# main.net
KiCad netlist of a schematic drawn in Altium Designer
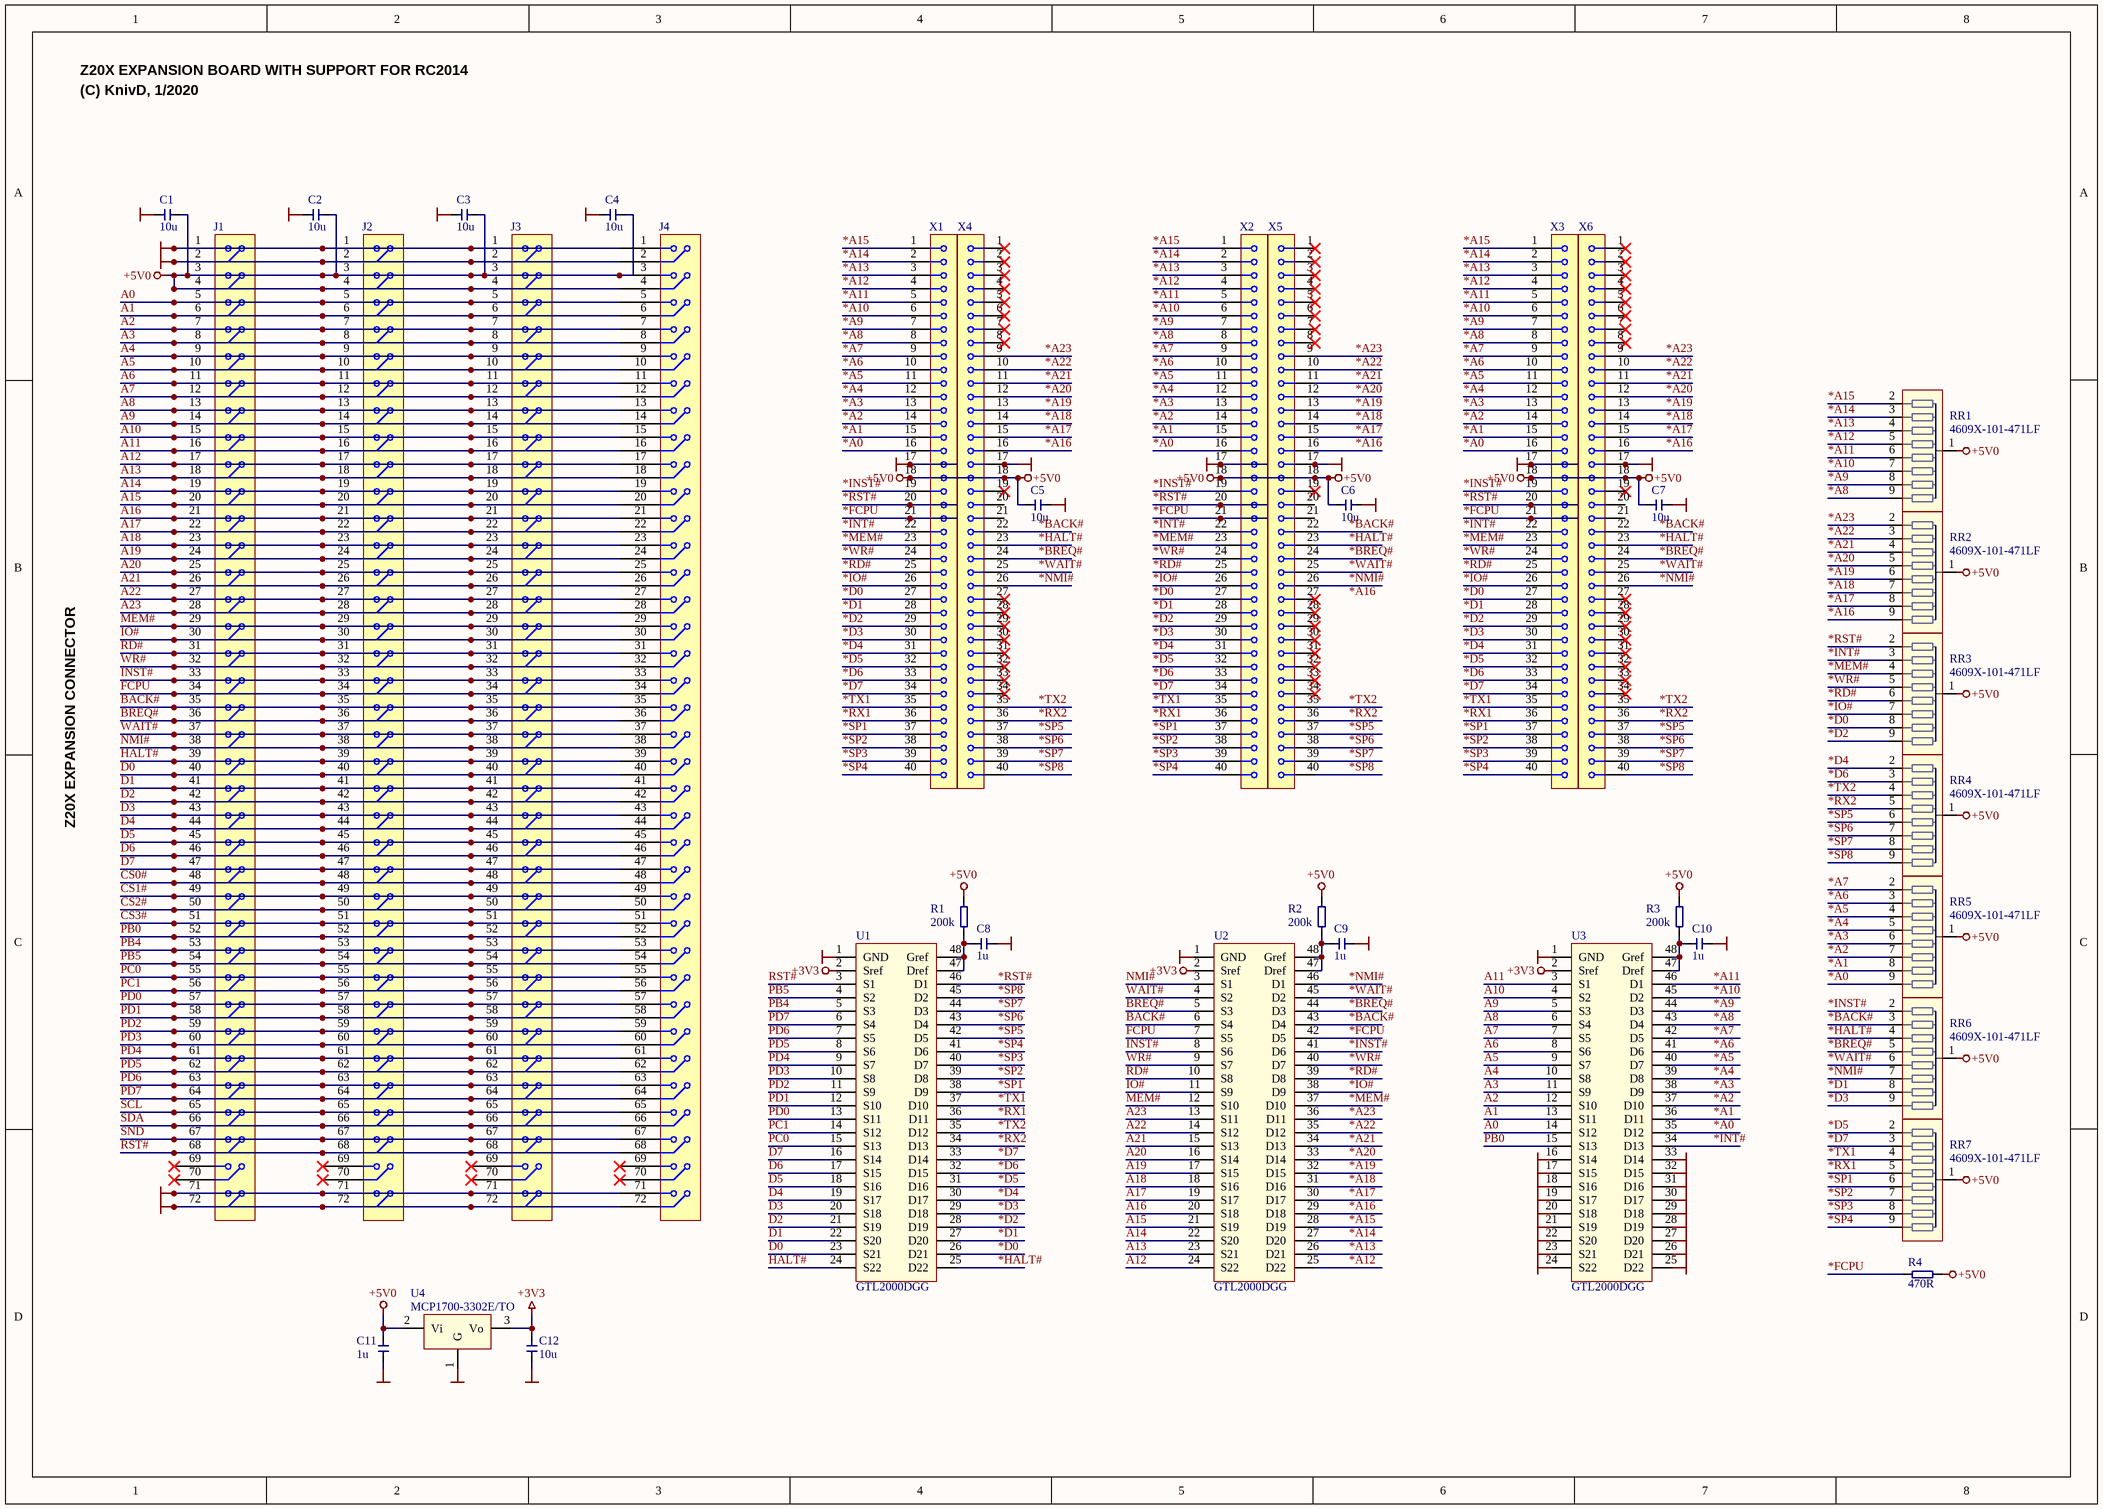
[diagram p0: main.SchDoc]

(export (version "E")
  (design (tool "Eeschema 10.0.6"))
  (components
    (comp (ref "C1")
      (value "10u")
      (footprint "CAPRR508-350X500X500")
      (description "Capacitor")
      (libsource (lib "Discretes") (part "Capacitor"))
    )
    (comp (ref "C2")
      (value "10u")
      (footprint "CAPRR508-350X500X500")
      (description "Capacitor")
      (libsource (lib "Discretes") (part "Capacitor"))
    )
    (comp (ref "C3")
      (value "10u")
      (footprint "CAPRR508-350X500X500")
      (description "Capacitor")
      (libsource (lib "Discretes") (part "Capacitor"))
    )
    (comp (ref "C4")
      (value "10u")
      (footprint "CAPRR508-350X500X500")
      (description "Capacitor")
      (libsource (lib "Discretes") (part "Capacitor"))
    )
    (comp (ref "C5")
      (value "10u")
      (footprint "CAPRR508-350X500X500")
      (description "Capacitor")
      (libsource (lib "Discretes") (part "Capacitor"))
    )
    (comp (ref "C6")
      (value "10u")
      (footprint "CAPRR508-350X500X500")
      (description "Capacitor")
      (libsource (lib "Discretes") (part "Capacitor"))
    )
    (comp (ref "C7")
      (value "10u")
      (footprint "CAPRR508-350X500X500")
      (description "Capacitor")
      (libsource (lib "Discretes") (part "Capacitor"))
    )
    (comp (ref "C8")
      (value "1u")
      (footprint "CAPRR508-350X500X500")
      (description "Capacitor")
      (libsource (lib "Discretes") (part "Capacitor"))
    )
    (comp (ref "C9")
      (value "1u")
      (footprint "CAPRR508-350X500X500")
      (description "Capacitor")
      (libsource (lib "Discretes") (part "Capacitor"))
    )
    (comp (ref "C10")
      (value "1u")
      (footprint "CAPRR508-350X500X500")
      (description "Capacitor")
      (libsource (lib "Discretes") (part "Capacitor"))
    )
    (comp (ref "C11")
      (value "1u")
      (footprint "CAPRR508-350X500X500")
      (description "Capacitor")
      (libsource (lib "Discretes") (part "Capacitor"))
    )
    (comp (ref "C12")
      (value "10u")
      (footprint "CAPRR508-350X500X500")
      (description "Capacitor")
      (libsource (lib "Discretes") (part "Capacitor"))
    )
    (comp (ref "J1")
      (value "~")
      (footprint "2011-2X36S-F")
      (description "Dual row, 72-way connector")
      (libsource (lib "Connectors") (part "Connector 2x36"))
    )
    (comp (ref "J2")
      (value "~")
      (footprint "2011-2X36S-F")
      (description "Dual row, 72-way connector")
      (libsource (lib "Connectors") (part "Connector 2x36"))
    )
    (comp (ref "J3")
      (value "~")
      (footprint "2011-2X36S-F")
      (description "Dual row, 72-way connector")
      (libsource (lib "Connectors") (part "Connector 2x36"))
    )
    (comp (ref "J4")
      (value "~")
      (footprint "2011-2X36S-F")
      (description "Dual row, 72-way connector")
      (libsource (lib "Connectors") (part "Connector 2x36"))
    )
    (comp (ref "R1")
      (value "200k")
      (footprint "RES1016-660X250")
      (description "Resistor")
      (libsource (lib "") (part "Resistor_1"))
    )
    (comp (ref "R2")
      (value "200k")
      (footprint "RES1016-660X250")
      (description "Resistor")
      (libsource (lib "") (part "Resistor_1"))
    )
    (comp (ref "R3")
      (value "200k")
      (footprint "RES1016-660X250")
      (description "Resistor")
      (libsource (lib "") (part "Resistor_1"))
    )
    (comp (ref "R4")
      (value "470R")
      (footprint "RES1016-660X250")
      (description "Resistor")
      (libsource (lib "Discretes") (part "Resistor"))
    )
    (comp (ref "RR1")
      (value "4609X-101-471LF")
      (footprint "RN_BOURNS_4600X")
      (description "Resistor Array (Bussed)")
      (libsource (lib "Misc") (part "Resistor Array x8 (BUSSED)"))
    )
    (comp (ref "RR2")
      (value "4609X-101-471LF")
      (footprint "RN_BOURNS_4600X")
      (description "Resistor Array (Bussed)")
      (libsource (lib "Misc") (part "Resistor Array x8 (BUSSED)"))
    )
    (comp (ref "RR3")
      (value "4609X-101-471LF")
      (footprint "RN_BOURNS_4600X")
      (description "Resistor Array (Bussed)")
      (libsource (lib "Misc") (part "Resistor Array x8 (BUSSED)"))
    )
    (comp (ref "RR4")
      (value "4609X-101-471LF")
      (footprint "RN_BOURNS_4600X")
      (description "Resistor Array (Bussed)")
      (libsource (lib "Misc") (part "Resistor Array x8 (BUSSED)"))
    )
    (comp (ref "RR5")
      (value "4609X-101-471LF")
      (footprint "RN_BOURNS_4600X")
      (description "Resistor Array (Bussed)")
      (libsource (lib "Misc") (part "Resistor Array x8 (BUSSED)"))
    )
    (comp (ref "RR6")
      (value "4609X-101-471LF")
      (footprint "RN_BOURNS_4600X")
      (description "Resistor Array (Bussed)")
      (libsource (lib "Misc") (part "Resistor Array x8 (BUSSED)"))
    )
    (comp (ref "RR7")
      (value "4609X-101-471LF")
      (footprint "RN_BOURNS_4600X")
      (description "Resistor Array (Bussed)")
      (libsource (lib "Misc") (part "Resistor Array x8 (BUSSED)"))
    )
    (comp (ref "U1")
      (value "GTL2000DGG")
      (footprint "SOP50P810X120-48N")
      (description "22-bit bi-directional low voltage translator")
      (fields (field (name "MANUFACTURER") "NXP"))
      (libsource (lib "IC Interface") (part "GTL2000"))
    )
    (comp (ref "U2")
      (value "GTL2000DGG")
      (footprint "SOP50P810X120-48N")
      (description "22-bit bi-directional low voltage translator")
      (fields (field (name "MANUFACTURER") "NXP"))
      (libsource (lib "IC Interface") (part "GTL2000"))
    )
    (comp (ref "U3")
      (value "GTL2000DGG")
      (footprint "SOP50P810X120-48N")
      (description "22-bit bi-directional low voltage translator")
      (fields (field (name "MANUFACTURER") "NXP"))
      (libsource (lib "IC Interface") (part "GTL2000"))
    )
    (comp (ref "U4")
      (value "MCP1700-3302E/TO")
      (footprint "TO-92AA-P254")
      (description "3-terminal 250mA positive voltage regulator")
      (fields (field (name "MANUFACTURER") "Microchip"))
      (libsource (lib "IC Power Supply") (part "78Lxx"))
    )
    (comp (ref "X1")
      (value "SIL40-F")
      (footprint "2011-1X40S")
      (description "Single row, 40-way connector")
      (libsource (lib "Connectors") (part "Connector 1x40"))
    )
    (comp (ref "X2")
      (value "SIL40-F")
      (footprint "2011-1X40S")
      (description "Single row, 40-way connector")
      (libsource (lib "Connectors") (part "Connector 1x40"))
    )
    (comp (ref "X3")
      (value "SIL40-F")
      (footprint "2011-1X40S")
      (description "Single row, 40-way connector")
      (libsource (lib "Connectors") (part "Connector 1x40"))
    )
    (comp (ref "X4")
      (value "SIL40-F")
      (footprint "2011-1X40S")
      (description "Single row, 40-way connector")
      (libsource (lib "Connectors") (part "Connector 1x40"))
    )
    (comp (ref "X5")
      (value "SIL40-F")
      (footprint "2011-1X40S")
      (description "Single row, 40-way connector")
      (libsource (lib "Connectors") (part "Connector 1x40"))
    )
    (comp (ref "X6")
      (value "SIL40-F")
      (footprint "2011-1X40S")
      (description "Single row, 40-way connector")
      (libsource (lib "Connectors") (part "Connector 1x40"))
    )
  )
  (nets
    (net (code "1") (name "+3V3") (class "Default")
      (node (ref "C12") (pin "1") (pintype "passive"))
      (node (ref "U1") (pin "2") (pinfunction "Sref_2") (pintype "passive"))
      (node (ref "U2") (pin "2") (pinfunction "Sref_2") (pintype "passive"))
      (node (ref "U3") (pin "2") (pinfunction "Sref_2") (pintype "passive"))
      (node (ref "U4") (pin "3") (pinfunction "Vo_3") (pintype "passive"))
    )
    (net (code "2") (name "+5V0") (class "Default")
      (node (ref "C1") (pin "1") (pintype "passive"))
      (node (ref "C11") (pin "1") (pintype "passive"))
      (node (ref "C2") (pin "1") (pintype "passive"))
      (node (ref "C3") (pin "1") (pintype "passive"))
      (node (ref "C4") (pin "1") (pintype "passive"))
      (node (ref "C5") (pin "2") (pintype "passive"))
      (node (ref "C6") (pin "2") (pintype "passive"))
      (node (ref "C7") (pin "2") (pintype "passive"))
      (node (ref "J1") (pin "3") (pinfunction "3_3") (pintype "passive"))
      (node (ref "J1") (pin "4") (pinfunction "4_4") (pintype "passive"))
      (node (ref "J2") (pin "3") (pinfunction "3_3") (pintype "passive"))
      (node (ref "J2") (pin "4") (pinfunction "4_4") (pintype "passive"))
      (node (ref "J3") (pin "3") (pinfunction "3_3") (pintype "passive"))
      (node (ref "J3") (pin "4") (pinfunction "4_4") (pintype "passive"))
      (node (ref "J4") (pin "3") (pinfunction "3_3") (pintype "passive"))
      (node (ref "J4") (pin "4") (pinfunction "4_4") (pintype "passive"))
      (node (ref "R1") (pin "1") (pintype "passive"))
      (node (ref "R2") (pin "1") (pintype "passive"))
      (node (ref "R3") (pin "1") (pintype "passive"))
      (node (ref "R4") (pin "2") (pintype "passive"))
      (node (ref "RR1") (pin "1") (pintype "passive"))
      (node (ref "RR2") (pin "1") (pintype "passive"))
      (node (ref "RR3") (pin "1") (pintype "passive"))
      (node (ref "RR4") (pin "1") (pintype "passive"))
      (node (ref "RR5") (pin "1") (pintype "passive"))
      (node (ref "RR6") (pin "1") (pintype "passive"))
      (node (ref "RR7") (pin "1") (pintype "passive"))
      (node (ref "U4") (pin "2") (pinfunction "Vi_2") (pintype "passive"))
      (node (ref "X1") (pin "18") (pinfunction "18_18") (pintype "passive"))
      (node (ref "X2") (pin "18") (pinfunction "18_18") (pintype "passive"))
      (node (ref "X3") (pin "18") (pinfunction "18_18") (pintype "passive"))
      (node (ref "X4") (pin "18") (pinfunction "18_18") (pintype "passive"))
      (node (ref "X5") (pin "18") (pinfunction "18_18") (pintype "passive"))
      (node (ref "X6") (pin "18") (pinfunction "18_18") (pintype "passive"))
    )
    (net (code "3") (name "/*A0") (class "Default")
      (node (ref "RR5") (pin "9") (pintype "passive"))
      (node (ref "U3") (pin "35") (pinfunction "D12_35") (pintype "passive"))
      (node (ref "X1") (pin "16") (pinfunction "16_16") (pintype "passive"))
      (node (ref "X2") (pin "16") (pinfunction "16_16") (pintype "passive"))
      (node (ref "X3") (pin "16") (pinfunction "16_16") (pintype "passive"))
    )
    (net (code "4") (name "/*A1") (class "Default")
      (node (ref "RR5") (pin "8") (pintype "passive"))
      (node (ref "U3") (pin "36") (pinfunction "D11_36") (pintype "passive"))
      (node (ref "X1") (pin "15") (pinfunction "15_15") (pintype "passive"))
      (node (ref "X2") (pin "15") (pinfunction "15_15") (pintype "passive"))
      (node (ref "X3") (pin "15") (pinfunction "15_15") (pintype "passive"))
    )
    (net (code "5") (name "/*A2") (class "Default")
      (node (ref "RR5") (pin "7") (pintype "passive"))
      (node (ref "U3") (pin "37") (pinfunction "D10_37") (pintype "passive"))
      (node (ref "X1") (pin "14") (pinfunction "14_14") (pintype "passive"))
      (node (ref "X2") (pin "14") (pinfunction "14_14") (pintype "passive"))
      (node (ref "X3") (pin "14") (pinfunction "14_14") (pintype "passive"))
    )
    (net (code "6") (name "/*A3") (class "Default")
      (node (ref "RR5") (pin "6") (pintype "passive"))
      (node (ref "U3") (pin "38") (pinfunction "D9_38") (pintype "passive"))
      (node (ref "X1") (pin "13") (pinfunction "13_13") (pintype "passive"))
      (node (ref "X2") (pin "13") (pinfunction "13_13") (pintype "passive"))
      (node (ref "X3") (pin "13") (pinfunction "13_13") (pintype "passive"))
    )
    (net (code "7") (name "/*A4") (class "Default")
      (node (ref "RR5") (pin "5") (pintype "passive"))
      (node (ref "U3") (pin "39") (pinfunction "D8_39") (pintype "passive"))
      (node (ref "X1") (pin "12") (pinfunction "12_12") (pintype "passive"))
      (node (ref "X2") (pin "12") (pinfunction "12_12") (pintype "passive"))
      (node (ref "X3") (pin "12") (pinfunction "12_12") (pintype "passive"))
    )
    (net (code "8") (name "/*A5") (class "Default")
      (node (ref "RR5") (pin "4") (pintype "passive"))
      (node (ref "U3") (pin "40") (pinfunction "D7_40") (pintype "passive"))
      (node (ref "X1") (pin "11") (pinfunction "11_11") (pintype "passive"))
      (node (ref "X2") (pin "11") (pinfunction "11_11") (pintype "passive"))
      (node (ref "X3") (pin "11") (pinfunction "11_11") (pintype "passive"))
    )
    (net (code "9") (name "/*A6") (class "Default")
      (node (ref "RR5") (pin "3") (pintype "passive"))
      (node (ref "U3") (pin "41") (pinfunction "D6_41") (pintype "passive"))
      (node (ref "X1") (pin "10") (pinfunction "10_10") (pintype "passive"))
      (node (ref "X2") (pin "10") (pinfunction "10_10") (pintype "passive"))
      (node (ref "X3") (pin "10") (pinfunction "10_10") (pintype "passive"))
    )
    (net (code "10") (name "/*A7") (class "Default")
      (node (ref "RR5") (pin "2") (pintype "passive"))
      (node (ref "U3") (pin "42") (pinfunction "D5_42") (pintype "passive"))
      (node (ref "X1") (pin "9") (pinfunction "9_9") (pintype "passive"))
      (node (ref "X2") (pin "9") (pinfunction "9_9") (pintype "passive"))
      (node (ref "X3") (pin "9") (pinfunction "9_9") (pintype "passive"))
    )
    (net (code "11") (name "/*A8") (class "Default")
      (node (ref "RR1") (pin "9") (pintype "passive"))
      (node (ref "U3") (pin "43") (pinfunction "D4_43") (pintype "passive"))
      (node (ref "X1") (pin "8") (pinfunction "8_8") (pintype "passive"))
      (node (ref "X2") (pin "8") (pinfunction "8_8") (pintype "passive"))
      (node (ref "X3") (pin "8") (pinfunction "8_8") (pintype "passive"))
    )
    (net (code "12") (name "/*A9") (class "Default")
      (node (ref "RR1") (pin "8") (pintype "passive"))
      (node (ref "U3") (pin "44") (pinfunction "D3_44") (pintype "passive"))
      (node (ref "X1") (pin "7") (pinfunction "7_7") (pintype "passive"))
      (node (ref "X2") (pin "7") (pinfunction "7_7") (pintype "passive"))
      (node (ref "X3") (pin "7") (pinfunction "7_7") (pintype "passive"))
    )
    (net (code "13") (name "/*A10") (class "Default")
      (node (ref "RR1") (pin "7") (pintype "passive"))
      (node (ref "U3") (pin "45") (pinfunction "D2_45") (pintype "passive"))
      (node (ref "X1") (pin "6") (pinfunction "6_6") (pintype "passive"))
      (node (ref "X2") (pin "6") (pinfunction "6_6") (pintype "passive"))
      (node (ref "X3") (pin "6") (pinfunction "6_6") (pintype "passive"))
    )
    (net (code "14") (name "/*A11") (class "Default")
      (node (ref "RR1") (pin "6") (pintype "passive"))
      (node (ref "U3") (pin "46") (pinfunction "D1_46") (pintype "passive"))
      (node (ref "X1") (pin "5") (pinfunction "5_5") (pintype "passive"))
      (node (ref "X2") (pin "5") (pinfunction "5_5") (pintype "passive"))
      (node (ref "X3") (pin "5") (pinfunction "5_5") (pintype "passive"))
    )
    (net (code "15") (name "/*A12") (class "Default")
      (node (ref "RR1") (pin "5") (pintype "passive"))
      (node (ref "U2") (pin "25") (pinfunction "D22_25") (pintype "passive"))
      (node (ref "X1") (pin "4") (pinfunction "4_4") (pintype "passive"))
      (node (ref "X2") (pin "4") (pinfunction "4_4") (pintype "passive"))
      (node (ref "X3") (pin "4") (pinfunction "4_4") (pintype "passive"))
    )
    (net (code "16") (name "/*A13") (class "Default")
      (node (ref "RR1") (pin "4") (pintype "passive"))
      (node (ref "U2") (pin "26") (pinfunction "D21_26") (pintype "passive"))
      (node (ref "X1") (pin "3") (pinfunction "3_3") (pintype "passive"))
      (node (ref "X2") (pin "3") (pinfunction "3_3") (pintype "passive"))
      (node (ref "X3") (pin "3") (pinfunction "3_3") (pintype "passive"))
    )
    (net (code "17") (name "/*A14") (class "Default")
      (node (ref "RR1") (pin "3") (pintype "passive"))
      (node (ref "U2") (pin "27") (pinfunction "D20_27") (pintype "passive"))
      (node (ref "X1") (pin "2") (pinfunction "2_2") (pintype "passive"))
      (node (ref "X2") (pin "2") (pinfunction "2_2") (pintype "passive"))
      (node (ref "X3") (pin "2") (pinfunction "2_2") (pintype "passive"))
    )
    (net (code "18") (name "/*A15") (class "Default")
      (node (ref "RR1") (pin "2") (pintype "passive"))
      (node (ref "U2") (pin "28") (pinfunction "D19_28") (pintype "passive"))
      (node (ref "X1") (pin "1") (pinfunction "1_1") (pintype "passive"))
      (node (ref "X2") (pin "1") (pinfunction "1_1") (pintype "passive"))
      (node (ref "X3") (pin "1") (pinfunction "1_1") (pintype "passive"))
    )
    (net (code "19") (name "/*A16") (class "Default")
      (node (ref "RR2") (pin "9") (pintype "passive"))
      (node (ref "U2") (pin "29") (pinfunction "D18_29") (pintype "passive"))
      (node (ref "X4") (pin "16") (pinfunction "16_16") (pintype "passive"))
      (node (ref "X5") (pin "16") (pinfunction "16_16") (pintype "passive"))
      (node (ref "X6") (pin "16") (pinfunction "16_16") (pintype "passive"))
    )
    (net (code "20") (name "/*A17") (class "Default")
      (node (ref "RR2") (pin "8") (pintype "passive"))
      (node (ref "U2") (pin "30") (pinfunction "D17_30") (pintype "passive"))
      (node (ref "X4") (pin "15") (pinfunction "15_15") (pintype "passive"))
      (node (ref "X5") (pin "15") (pinfunction "15_15") (pintype "passive"))
      (node (ref "X6") (pin "15") (pinfunction "15_15") (pintype "passive"))
    )
    (net (code "21") (name "/*A18") (class "Default")
      (node (ref "RR2") (pin "7") (pintype "passive"))
      (node (ref "U2") (pin "31") (pinfunction "D16_31") (pintype "passive"))
      (node (ref "X4") (pin "14") (pinfunction "14_14") (pintype "passive"))
      (node (ref "X5") (pin "14") (pinfunction "14_14") (pintype "passive"))
      (node (ref "X6") (pin "14") (pinfunction "14_14") (pintype "passive"))
    )
    (net (code "22") (name "/*A19") (class "Default")
      (node (ref "RR2") (pin "6") (pintype "passive"))
      (node (ref "U2") (pin "32") (pinfunction "D15_32") (pintype "passive"))
      (node (ref "X4") (pin "13") (pinfunction "13_13") (pintype "passive"))
      (node (ref "X5") (pin "13") (pinfunction "13_13") (pintype "passive"))
      (node (ref "X6") (pin "13") (pinfunction "13_13") (pintype "passive"))
    )
    (net (code "23") (name "/*A20") (class "Default")
      (node (ref "RR2") (pin "5") (pintype "passive"))
      (node (ref "U2") (pin "33") (pinfunction "D14_33") (pintype "passive"))
      (node (ref "X4") (pin "12") (pinfunction "12_12") (pintype "passive"))
      (node (ref "X5") (pin "12") (pinfunction "12_12") (pintype "passive"))
      (node (ref "X6") (pin "12") (pinfunction "12_12") (pintype "passive"))
    )
    (net (code "24") (name "/*A21") (class "Default")
      (node (ref "RR2") (pin "4") (pintype "passive"))
      (node (ref "U2") (pin "34") (pinfunction "D13_34") (pintype "passive"))
      (node (ref "X4") (pin "11") (pinfunction "11_11") (pintype "passive"))
      (node (ref "X5") (pin "11") (pinfunction "11_11") (pintype "passive"))
      (node (ref "X6") (pin "11") (pinfunction "11_11") (pintype "passive"))
    )
    (net (code "25") (name "/*A22") (class "Default")
      (node (ref "RR2") (pin "3") (pintype "passive"))
      (node (ref "U2") (pin "35") (pinfunction "D12_35") (pintype "passive"))
      (node (ref "X4") (pin "10") (pinfunction "10_10") (pintype "passive"))
      (node (ref "X5") (pin "10") (pinfunction "10_10") (pintype "passive"))
      (node (ref "X6") (pin "10") (pinfunction "10_10") (pintype "passive"))
    )
    (net (code "26") (name "/*A23") (class "Default")
      (node (ref "RR2") (pin "2") (pintype "passive"))
      (node (ref "U2") (pin "36") (pinfunction "D11_36") (pintype "passive"))
      (node (ref "X4") (pin "9") (pinfunction "9_9") (pintype "passive"))
      (node (ref "X5") (pin "9") (pinfunction "9_9") (pintype "passive"))
      (node (ref "X6") (pin "9") (pinfunction "9_9") (pintype "passive"))
    )
    (net (code "27") (name "/*BACK#") (class "Default")
      (node (ref "RR6") (pin "3") (pintype "passive"))
      (node (ref "U2") (pin "43") (pinfunction "D4_43") (pintype "passive"))
      (node (ref "X4") (pin "22") (pinfunction "22_22") (pintype "passive"))
      (node (ref "X5") (pin "22") (pinfunction "22_22") (pintype "passive"))
      (node (ref "X6") (pin "22") (pinfunction "22_22") (pintype "passive"))
    )
    (net (code "28") (name "/*BREQ#") (class "Default")
      (node (ref "RR6") (pin "5") (pintype "passive"))
      (node (ref "U2") (pin "44") (pinfunction "D3_44") (pintype "passive"))
      (node (ref "X4") (pin "24") (pinfunction "24_24") (pintype "passive"))
      (node (ref "X5") (pin "24") (pinfunction "24_24") (pintype "passive"))
      (node (ref "X6") (pin "24") (pinfunction "24_24") (pintype "passive"))
    )
    (net (code "29") (name "/*D0") (class "Default")
      (node (ref "RR3") (pin "8") (pintype "passive"))
      (node (ref "U1") (pin "26") (pinfunction "D21_26") (pintype "passive"))
      (node (ref "X1") (pin "27") (pinfunction "27_27") (pintype "passive"))
      (node (ref "X2") (pin "27") (pinfunction "27_27") (pintype "passive"))
      (node (ref "X3") (pin "27") (pinfunction "27_27") (pintype "passive"))
    )
    (net (code "30") (name "/*D1") (class "Default")
      (node (ref "RR6") (pin "8") (pintype "passive"))
      (node (ref "U1") (pin "27") (pinfunction "D20_27") (pintype "passive"))
      (node (ref "X1") (pin "28") (pinfunction "28_28") (pintype "passive"))
      (node (ref "X2") (pin "28") (pinfunction "28_28") (pintype "passive"))
      (node (ref "X3") (pin "28") (pinfunction "28_28") (pintype "passive"))
    )
    (net (code "31") (name "/*D2") (class "Default")
      (node (ref "RR3") (pin "9") (pintype "passive"))
      (node (ref "U1") (pin "28") (pinfunction "D19_28") (pintype "passive"))
      (node (ref "X1") (pin "29") (pinfunction "29_29") (pintype "passive"))
      (node (ref "X2") (pin "29") (pinfunction "29_29") (pintype "passive"))
      (node (ref "X3") (pin "29") (pinfunction "29_29") (pintype "passive"))
    )
    (net (code "32") (name "/*D3") (class "Default")
      (node (ref "RR6") (pin "9") (pintype "passive"))
      (node (ref "U1") (pin "29") (pinfunction "D18_29") (pintype "passive"))
      (node (ref "X1") (pin "30") (pinfunction "30_30") (pintype "passive"))
      (node (ref "X2") (pin "30") (pinfunction "30_30") (pintype "passive"))
      (node (ref "X3") (pin "30") (pinfunction "30_30") (pintype "passive"))
    )
    (net (code "33") (name "/*D4") (class "Default")
      (node (ref "RR4") (pin "2") (pintype "passive"))
      (node (ref "U1") (pin "30") (pinfunction "D17_30") (pintype "passive"))
      (node (ref "X1") (pin "31") (pinfunction "31_31") (pintype "passive"))
      (node (ref "X2") (pin "31") (pinfunction "31_31") (pintype "passive"))
      (node (ref "X3") (pin "31") (pinfunction "31_31") (pintype "passive"))
    )
    (net (code "34") (name "/*D5") (class "Default")
      (node (ref "RR7") (pin "2") (pintype "passive"))
      (node (ref "U1") (pin "31") (pinfunction "D16_31") (pintype "passive"))
      (node (ref "X1") (pin "32") (pinfunction "32_32") (pintype "passive"))
      (node (ref "X2") (pin "32") (pinfunction "32_32") (pintype "passive"))
      (node (ref "X3") (pin "32") (pinfunction "32_32") (pintype "passive"))
    )
    (net (code "35") (name "/*D6") (class "Default")
      (node (ref "RR4") (pin "3") (pintype "passive"))
      (node (ref "U1") (pin "32") (pinfunction "D15_32") (pintype "passive"))
      (node (ref "X1") (pin "33") (pinfunction "33_33") (pintype "passive"))
      (node (ref "X2") (pin "33") (pinfunction "33_33") (pintype "passive"))
      (node (ref "X3") (pin "33") (pinfunction "33_33") (pintype "passive"))
    )
    (net (code "36") (name "/*D7") (class "Default")
      (node (ref "RR7") (pin "3") (pintype "passive"))
      (node (ref "U1") (pin "33") (pinfunction "D14_33") (pintype "passive"))
      (node (ref "X1") (pin "34") (pinfunction "34_34") (pintype "passive"))
      (node (ref "X2") (pin "34") (pinfunction "34_34") (pintype "passive"))
      (node (ref "X3") (pin "34") (pinfunction "34_34") (pintype "passive"))
    )
    (net (code "37") (name "/*FCPU") (class "Default")
      (node (ref "R4") (pin "1") (pintype "passive"))
      (node (ref "U2") (pin "42") (pinfunction "D5_42") (pintype "passive"))
      (node (ref "X1") (pin "21") (pinfunction "21_21") (pintype "passive"))
      (node (ref "X2") (pin "21") (pinfunction "21_21") (pintype "passive"))
      (node (ref "X3") (pin "21") (pinfunction "21_21") (pintype "passive"))
      (node (ref "X4") (pin "21") (pinfunction "21_21") (pintype "passive"))
      (node (ref "X5") (pin "21") (pinfunction "21_21") (pintype "passive"))
      (node (ref "X6") (pin "21") (pinfunction "21_21") (pintype "passive"))
    )
    (net (code "38") (name "/*HALT#") (class "Default")
      (node (ref "RR6") (pin "4") (pintype "passive"))
      (node (ref "U1") (pin "25") (pinfunction "D22_25") (pintype "passive"))
      (node (ref "X4") (pin "23") (pinfunction "23_23") (pintype "passive"))
      (node (ref "X5") (pin "23") (pinfunction "23_23") (pintype "passive"))
      (node (ref "X6") (pin "23") (pinfunction "23_23") (pintype "passive"))
    )
    (net (code "39") (name "/*INST#") (class "Default")
      (node (ref "RR6") (pin "2") (pintype "passive"))
      (node (ref "U2") (pin "41") (pinfunction "D6_41") (pintype "passive"))
      (node (ref "X1") (pin "19") (pinfunction "19_19") (pintype "passive"))
      (node (ref "X2") (pin "19") (pinfunction "19_19") (pintype "passive"))
      (node (ref "X3") (pin "19") (pinfunction "19_19") (pintype "passive"))
    )
    (net (code "40") (name "/*INT#") (class "Default")
      (node (ref "RR3") (pin "3") (pintype "passive"))
      (node (ref "U3") (pin "34") (pinfunction "D13_34") (pintype "passive"))
      (node (ref "X1") (pin "22") (pinfunction "22_22") (pintype "passive"))
      (node (ref "X2") (pin "22") (pinfunction "22_22") (pintype "passive"))
      (node (ref "X3") (pin "22") (pinfunction "22_22") (pintype "passive"))
    )
    (net (code "41") (name "/*IO#") (class "Default")
      (node (ref "RR3") (pin "7") (pintype "passive"))
      (node (ref "U2") (pin "38") (pinfunction "D9_38") (pintype "passive"))
      (node (ref "X1") (pin "26") (pinfunction "26_26") (pintype "passive"))
      (node (ref "X2") (pin "26") (pinfunction "26_26") (pintype "passive"))
      (node (ref "X3") (pin "26") (pinfunction "26_26") (pintype "passive"))
    )
    (net (code "42") (name "/*MEM#") (class "Default")
      (node (ref "RR3") (pin "4") (pintype "passive"))
      (node (ref "U2") (pin "37") (pinfunction "D10_37") (pintype "passive"))
      (node (ref "X1") (pin "23") (pinfunction "23_23") (pintype "passive"))
      (node (ref "X2") (pin "23") (pinfunction "23_23") (pintype "passive"))
      (node (ref "X3") (pin "23") (pinfunction "23_23") (pintype "passive"))
    )
    (net (code "43") (name "/*NMI#") (class "Default")
      (node (ref "RR6") (pin "7") (pintype "passive"))
      (node (ref "U2") (pin "46") (pinfunction "D1_46") (pintype "passive"))
      (node (ref "X4") (pin "26") (pinfunction "26_26") (pintype "passive"))
      (node (ref "X5") (pin "26") (pinfunction "26_26") (pintype "passive"))
      (node (ref "X6") (pin "26") (pinfunction "26_26") (pintype "passive"))
    )
    (net (code "44") (name "/*RD#") (class "Default")
      (node (ref "RR3") (pin "6") (pintype "passive"))
      (node (ref "U2") (pin "39") (pinfunction "D8_39") (pintype "passive"))
      (node (ref "X1") (pin "25") (pinfunction "25_25") (pintype "passive"))
      (node (ref "X2") (pin "25") (pinfunction "25_25") (pintype "passive"))
      (node (ref "X3") (pin "25") (pinfunction "25_25") (pintype "passive"))
    )
    (net (code "45") (name "/*RST#") (class "Default")
      (node (ref "RR3") (pin "2") (pintype "passive"))
      (node (ref "U1") (pin "46") (pinfunction "D1_46") (pintype "passive"))
      (node (ref "X1") (pin "20") (pinfunction "20_20") (pintype "passive"))
      (node (ref "X2") (pin "20") (pinfunction "20_20") (pintype "passive"))
      (node (ref "X3") (pin "20") (pinfunction "20_20") (pintype "passive"))
      (node (ref "X4") (pin "20") (pinfunction "20_20") (pintype "passive"))
      (node (ref "X5") (pin "20") (pinfunction "20_20") (pintype "passive"))
      (node (ref "X6") (pin "20") (pinfunction "20_20") (pintype "passive"))
    )
    (net (code "46") (name "/*RX1") (class "Default")
      (node (ref "RR7") (pin "5") (pintype "passive"))
      (node (ref "U1") (pin "36") (pinfunction "D11_36") (pintype "passive"))
      (node (ref "X1") (pin "36") (pinfunction "36_36") (pintype "passive"))
      (node (ref "X2") (pin "36") (pinfunction "36_36") (pintype "passive"))
      (node (ref "X3") (pin "36") (pinfunction "36_36") (pintype "passive"))
    )
    (net (code "47") (name "/*RX2") (class "Default")
      (node (ref "RR4") (pin "5") (pintype "passive"))
      (node (ref "U1") (pin "34") (pinfunction "D13_34") (pintype "passive"))
      (node (ref "X4") (pin "36") (pinfunction "36_36") (pintype "passive"))
      (node (ref "X5") (pin "36") (pinfunction "36_36") (pintype "passive"))
      (node (ref "X6") (pin "36") (pinfunction "36_36") (pintype "passive"))
    )
    (net (code "48") (name "/*SP1") (class "Default")
      (node (ref "RR7") (pin "6") (pintype "passive"))
      (node (ref "U1") (pin "38") (pinfunction "D9_38") (pintype "passive"))
      (node (ref "X1") (pin "37") (pinfunction "37_37") (pintype "passive"))
      (node (ref "X2") (pin "37") (pinfunction "37_37") (pintype "passive"))
      (node (ref "X3") (pin "37") (pinfunction "37_37") (pintype "passive"))
    )
    (net (code "49") (name "/*SP2") (class "Default")
      (node (ref "RR7") (pin "7") (pintype "passive"))
      (node (ref "U1") (pin "39") (pinfunction "D8_39") (pintype "passive"))
      (node (ref "X1") (pin "38") (pinfunction "38_38") (pintype "passive"))
      (node (ref "X2") (pin "38") (pinfunction "38_38") (pintype "passive"))
      (node (ref "X3") (pin "38") (pinfunction "38_38") (pintype "passive"))
    )
    (net (code "50") (name "/*SP3") (class "Default")
      (node (ref "RR7") (pin "8") (pintype "passive"))
      (node (ref "U1") (pin "40") (pinfunction "D7_40") (pintype "passive"))
      (node (ref "X1") (pin "39") (pinfunction "39_39") (pintype "passive"))
      (node (ref "X2") (pin "39") (pinfunction "39_39") (pintype "passive"))
      (node (ref "X3") (pin "39") (pinfunction "39_39") (pintype "passive"))
    )
    (net (code "51") (name "/*SP4") (class "Default")
      (node (ref "RR7") (pin "9") (pintype "passive"))
      (node (ref "U1") (pin "41") (pinfunction "D6_41") (pintype "passive"))
      (node (ref "X1") (pin "40") (pinfunction "40_40") (pintype "passive"))
      (node (ref "X2") (pin "40") (pinfunction "40_40") (pintype "passive"))
      (node (ref "X3") (pin "40") (pinfunction "40_40") (pintype "passive"))
    )
    (net (code "52") (name "/*SP5") (class "Default")
      (node (ref "RR4") (pin "6") (pintype "passive"))
      (node (ref "U1") (pin "42") (pinfunction "D5_42") (pintype "passive"))
      (node (ref "X4") (pin "37") (pinfunction "37_37") (pintype "passive"))
      (node (ref "X5") (pin "37") (pinfunction "37_37") (pintype "passive"))
      (node (ref "X6") (pin "37") (pinfunction "37_37") (pintype "passive"))
    )
    (net (code "53") (name "/*SP6") (class "Default")
      (node (ref "RR4") (pin "7") (pintype "passive"))
      (node (ref "U1") (pin "43") (pinfunction "D4_43") (pintype "passive"))
      (node (ref "X4") (pin "38") (pinfunction "38_38") (pintype "passive"))
      (node (ref "X5") (pin "38") (pinfunction "38_38") (pintype "passive"))
      (node (ref "X6") (pin "38") (pinfunction "38_38") (pintype "passive"))
    )
    (net (code "54") (name "/*SP7") (class "Default")
      (node (ref "RR4") (pin "8") (pintype "passive"))
      (node (ref "U1") (pin "44") (pinfunction "D3_44") (pintype "passive"))
      (node (ref "X4") (pin "39") (pinfunction "39_39") (pintype "passive"))
      (node (ref "X5") (pin "39") (pinfunction "39_39") (pintype "passive"))
      (node (ref "X6") (pin "39") (pinfunction "39_39") (pintype "passive"))
    )
    (net (code "55") (name "/*SP8") (class "Default")
      (node (ref "RR4") (pin "9") (pintype "passive"))
      (node (ref "U1") (pin "45") (pinfunction "D2_45") (pintype "passive"))
      (node (ref "X4") (pin "40") (pinfunction "40_40") (pintype "passive"))
      (node (ref "X5") (pin "40") (pinfunction "40_40") (pintype "passive"))
      (node (ref "X6") (pin "40") (pinfunction "40_40") (pintype "passive"))
    )
    (net (code "56") (name "/*TX1") (class "Default")
      (node (ref "RR7") (pin "4") (pintype "passive"))
      (node (ref "U1") (pin "37") (pinfunction "D10_37") (pintype "passive"))
      (node (ref "X1") (pin "35") (pinfunction "35_35") (pintype "passive"))
      (node (ref "X2") (pin "35") (pinfunction "35_35") (pintype "passive"))
      (node (ref "X3") (pin "35") (pinfunction "35_35") (pintype "passive"))
    )
    (net (code "57") (name "/*TX2") (class "Default")
      (node (ref "RR4") (pin "4") (pintype "passive"))
      (node (ref "U1") (pin "35") (pinfunction "D12_35") (pintype "passive"))
      (node (ref "X4") (pin "35") (pinfunction "35_35") (pintype "passive"))
      (node (ref "X5") (pin "35") (pinfunction "35_35") (pintype "passive"))
      (node (ref "X6") (pin "35") (pinfunction "35_35") (pintype "passive"))
    )
    (net (code "58") (name "/*WAIT#") (class "Default")
      (node (ref "RR6") (pin "6") (pintype "passive"))
      (node (ref "U2") (pin "45") (pinfunction "D2_45") (pintype "passive"))
      (node (ref "X4") (pin "25") (pinfunction "25_25") (pintype "passive"))
      (node (ref "X5") (pin "25") (pinfunction "25_25") (pintype "passive"))
      (node (ref "X6") (pin "25") (pinfunction "25_25") (pintype "passive"))
    )
    (net (code "59") (name "/*WR#") (class "Default")
      (node (ref "RR3") (pin "5") (pintype "passive"))
      (node (ref "U2") (pin "40") (pinfunction "D7_40") (pintype "passive"))
      (node (ref "X1") (pin "24") (pinfunction "24_24") (pintype "passive"))
      (node (ref "X2") (pin "24") (pinfunction "24_24") (pintype "passive"))
      (node (ref "X3") (pin "24") (pinfunction "24_24") (pintype "passive"))
    )
    (net (code "60") (name "/A0") (class "Default")
      (node (ref "J1") (pin "5") (pinfunction "5_5") (pintype "passive"))
      (node (ref "J2") (pin "5") (pinfunction "5_5") (pintype "passive"))
      (node (ref "J3") (pin "5") (pinfunction "5_5") (pintype "passive"))
      (node (ref "J4") (pin "5") (pinfunction "5_5") (pintype "passive"))
      (node (ref "U3") (pin "14") (pinfunction "S12_14") (pintype "passive"))
    )
    (net (code "61") (name "/A1") (class "Default")
      (node (ref "J1") (pin "6") (pinfunction "6_6") (pintype "passive"))
      (node (ref "J2") (pin "6") (pinfunction "6_6") (pintype "passive"))
      (node (ref "J3") (pin "6") (pinfunction "6_6") (pintype "passive"))
      (node (ref "J4") (pin "6") (pinfunction "6_6") (pintype "passive"))
      (node (ref "U3") (pin "13") (pinfunction "S11_13") (pintype "passive"))
    )
    (net (code "62") (name "/A2") (class "Default")
      (node (ref "J1") (pin "7") (pinfunction "7_7") (pintype "passive"))
      (node (ref "J2") (pin "7") (pinfunction "7_7") (pintype "passive"))
      (node (ref "J3") (pin "7") (pinfunction "7_7") (pintype "passive"))
      (node (ref "J4") (pin "7") (pinfunction "7_7") (pintype "passive"))
      (node (ref "U3") (pin "12") (pinfunction "S10_12") (pintype "passive"))
    )
    (net (code "63") (name "/A3") (class "Default")
      (node (ref "J1") (pin "8") (pinfunction "8_8") (pintype "passive"))
      (node (ref "J2") (pin "8") (pinfunction "8_8") (pintype "passive"))
      (node (ref "J3") (pin "8") (pinfunction "8_8") (pintype "passive"))
      (node (ref "J4") (pin "8") (pinfunction "8_8") (pintype "passive"))
      (node (ref "U3") (pin "11") (pinfunction "S9_11") (pintype "passive"))
    )
    (net (code "64") (name "/A4") (class "Default")
      (node (ref "J1") (pin "9") (pinfunction "9_9") (pintype "passive"))
      (node (ref "J2") (pin "9") (pinfunction "9_9") (pintype "passive"))
      (node (ref "J3") (pin "9") (pinfunction "9_9") (pintype "passive"))
      (node (ref "J4") (pin "9") (pinfunction "9_9") (pintype "passive"))
      (node (ref "U3") (pin "10") (pinfunction "S8_10") (pintype "passive"))
    )
    (net (code "65") (name "/A5") (class "Default")
      (node (ref "J1") (pin "10") (pinfunction "10_10") (pintype "passive"))
      (node (ref "J2") (pin "10") (pinfunction "10_10") (pintype "passive"))
      (node (ref "J3") (pin "10") (pinfunction "10_10") (pintype "passive"))
      (node (ref "J4") (pin "10") (pinfunction "10_10") (pintype "passive"))
      (node (ref "U3") (pin "9") (pinfunction "S7_9") (pintype "passive"))
    )
    (net (code "66") (name "/A6") (class "Default")
      (node (ref "J1") (pin "11") (pinfunction "11_11") (pintype "passive"))
      (node (ref "J2") (pin "11") (pinfunction "11_11") (pintype "passive"))
      (node (ref "J3") (pin "11") (pinfunction "11_11") (pintype "passive"))
      (node (ref "J4") (pin "11") (pinfunction "11_11") (pintype "passive"))
      (node (ref "U3") (pin "8") (pinfunction "S6_8") (pintype "passive"))
    )
    (net (code "67") (name "/A7") (class "Default")
      (node (ref "J1") (pin "12") (pinfunction "12_12") (pintype "passive"))
      (node (ref "J2") (pin "12") (pinfunction "12_12") (pintype "passive"))
      (node (ref "J3") (pin "12") (pinfunction "12_12") (pintype "passive"))
      (node (ref "J4") (pin "12") (pinfunction "12_12") (pintype "passive"))
      (node (ref "U3") (pin "7") (pinfunction "S5_7") (pintype "passive"))
    )
    (net (code "68") (name "/A8") (class "Default")
      (node (ref "J1") (pin "13") (pinfunction "13_13") (pintype "passive"))
      (node (ref "J2") (pin "13") (pinfunction "13_13") (pintype "passive"))
      (node (ref "J3") (pin "13") (pinfunction "13_13") (pintype "passive"))
      (node (ref "J4") (pin "13") (pinfunction "13_13") (pintype "passive"))
      (node (ref "U3") (pin "6") (pinfunction "S4_6") (pintype "passive"))
    )
    (net (code "69") (name "/A9") (class "Default")
      (node (ref "J1") (pin "14") (pinfunction "14_14") (pintype "passive"))
      (node (ref "J2") (pin "14") (pinfunction "14_14") (pintype "passive"))
      (node (ref "J3") (pin "14") (pinfunction "14_14") (pintype "passive"))
      (node (ref "J4") (pin "14") (pinfunction "14_14") (pintype "passive"))
      (node (ref "U3") (pin "5") (pinfunction "S3_5") (pintype "passive"))
    )
    (net (code "70") (name "/A10") (class "Default")
      (node (ref "J1") (pin "15") (pinfunction "15_15") (pintype "passive"))
      (node (ref "J2") (pin "15") (pinfunction "15_15") (pintype "passive"))
      (node (ref "J3") (pin "15") (pinfunction "15_15") (pintype "passive"))
      (node (ref "J4") (pin "15") (pinfunction "15_15") (pintype "passive"))
      (node (ref "U3") (pin "4") (pinfunction "S2_4") (pintype "passive"))
    )
    (net (code "71") (name "/A11") (class "Default")
      (node (ref "J1") (pin "16") (pinfunction "16_16") (pintype "passive"))
      (node (ref "J2") (pin "16") (pinfunction "16_16") (pintype "passive"))
      (node (ref "J3") (pin "16") (pinfunction "16_16") (pintype "passive"))
      (node (ref "J4") (pin "16") (pinfunction "16_16") (pintype "passive"))
      (node (ref "U3") (pin "3") (pinfunction "S1_3") (pintype "passive"))
    )
    (net (code "72") (name "/A12") (class "Default")
      (node (ref "J1") (pin "17") (pinfunction "17_17") (pintype "passive"))
      (node (ref "J2") (pin "17") (pinfunction "17_17") (pintype "passive"))
      (node (ref "J3") (pin "17") (pinfunction "17_17") (pintype "passive"))
      (node (ref "J4") (pin "17") (pinfunction "17_17") (pintype "passive"))
      (node (ref "U2") (pin "24") (pinfunction "S22_24") (pintype "passive"))
    )
    (net (code "73") (name "/A13") (class "Default")
      (node (ref "J1") (pin "18") (pinfunction "18_18") (pintype "passive"))
      (node (ref "J2") (pin "18") (pinfunction "18_18") (pintype "passive"))
      (node (ref "J3") (pin "18") (pinfunction "18_18") (pintype "passive"))
      (node (ref "J4") (pin "18") (pinfunction "18_18") (pintype "passive"))
      (node (ref "U2") (pin "23") (pinfunction "S21_23") (pintype "passive"))
    )
    (net (code "74") (name "/A14") (class "Default")
      (node (ref "J1") (pin "19") (pinfunction "19_19") (pintype "passive"))
      (node (ref "J2") (pin "19") (pinfunction "19_19") (pintype "passive"))
      (node (ref "J3") (pin "19") (pinfunction "19_19") (pintype "passive"))
      (node (ref "J4") (pin "19") (pinfunction "19_19") (pintype "passive"))
      (node (ref "U2") (pin "22") (pinfunction "S20_22") (pintype "passive"))
    )
    (net (code "75") (name "/A15") (class "Default")
      (node (ref "J1") (pin "20") (pinfunction "20_20") (pintype "passive"))
      (node (ref "J2") (pin "20") (pinfunction "20_20") (pintype "passive"))
      (node (ref "J3") (pin "20") (pinfunction "20_20") (pintype "passive"))
      (node (ref "J4") (pin "20") (pinfunction "20_20") (pintype "passive"))
      (node (ref "U2") (pin "21") (pinfunction "S19_21") (pintype "passive"))
    )
    (net (code "76") (name "/A16") (class "Default")
      (node (ref "J1") (pin "21") (pinfunction "21_21") (pintype "passive"))
      (node (ref "J2") (pin "21") (pinfunction "21_21") (pintype "passive"))
      (node (ref "J3") (pin "21") (pinfunction "21_21") (pintype "passive"))
      (node (ref "J4") (pin "21") (pinfunction "21_21") (pintype "passive"))
      (node (ref "U2") (pin "20") (pinfunction "S18_20") (pintype "passive"))
    )
    (net (code "77") (name "/A17") (class "Default")
      (node (ref "J1") (pin "22") (pinfunction "22_22") (pintype "passive"))
      (node (ref "J2") (pin "22") (pinfunction "22_22") (pintype "passive"))
      (node (ref "J3") (pin "22") (pinfunction "22_22") (pintype "passive"))
      (node (ref "J4") (pin "22") (pinfunction "22_22") (pintype "passive"))
      (node (ref "U2") (pin "19") (pinfunction "S17_19") (pintype "passive"))
    )
    (net (code "78") (name "/A18") (class "Default")
      (node (ref "J1") (pin "23") (pinfunction "23_23") (pintype "passive"))
      (node (ref "J2") (pin "23") (pinfunction "23_23") (pintype "passive"))
      (node (ref "J3") (pin "23") (pinfunction "23_23") (pintype "passive"))
      (node (ref "J4") (pin "23") (pinfunction "23_23") (pintype "passive"))
      (node (ref "U2") (pin "18") (pinfunction "S16_18") (pintype "passive"))
    )
    (net (code "79") (name "/A19") (class "Default")
      (node (ref "J1") (pin "24") (pinfunction "24_24") (pintype "passive"))
      (node (ref "J2") (pin "24") (pinfunction "24_24") (pintype "passive"))
      (node (ref "J3") (pin "24") (pinfunction "24_24") (pintype "passive"))
      (node (ref "J4") (pin "24") (pinfunction "24_24") (pintype "passive"))
      (node (ref "U2") (pin "17") (pinfunction "S15_17") (pintype "passive"))
    )
    (net (code "80") (name "/A20") (class "Default")
      (node (ref "J1") (pin "25") (pinfunction "25_25") (pintype "passive"))
      (node (ref "J2") (pin "25") (pinfunction "25_25") (pintype "passive"))
      (node (ref "J3") (pin "25") (pinfunction "25_25") (pintype "passive"))
      (node (ref "J4") (pin "25") (pinfunction "25_25") (pintype "passive"))
      (node (ref "U2") (pin "16") (pinfunction "S14_16") (pintype "passive"))
    )
    (net (code "81") (name "/A21") (class "Default")
      (node (ref "J1") (pin "26") (pinfunction "26_26") (pintype "passive"))
      (node (ref "J2") (pin "26") (pinfunction "26_26") (pintype "passive"))
      (node (ref "J3") (pin "26") (pinfunction "26_26") (pintype "passive"))
      (node (ref "J4") (pin "26") (pinfunction "26_26") (pintype "passive"))
      (node (ref "U2") (pin "15") (pinfunction "S13_15") (pintype "passive"))
    )
    (net (code "82") (name "/A22") (class "Default")
      (node (ref "J1") (pin "27") (pinfunction "27_27") (pintype "passive"))
      (node (ref "J2") (pin "27") (pinfunction "27_27") (pintype "passive"))
      (node (ref "J3") (pin "27") (pinfunction "27_27") (pintype "passive"))
      (node (ref "J4") (pin "27") (pinfunction "27_27") (pintype "passive"))
      (node (ref "U2") (pin "14") (pinfunction "S12_14") (pintype "passive"))
    )
    (net (code "83") (name "/A23") (class "Default")
      (node (ref "J1") (pin "28") (pinfunction "28_28") (pintype "passive"))
      (node (ref "J2") (pin "28") (pinfunction "28_28") (pintype "passive"))
      (node (ref "J3") (pin "28") (pinfunction "28_28") (pintype "passive"))
      (node (ref "J4") (pin "28") (pinfunction "28_28") (pintype "passive"))
      (node (ref "U2") (pin "13") (pinfunction "S11_13") (pintype "passive"))
    )
    (net (code "84") (name "/BACK#") (class "Default")
      (node (ref "J1") (pin "35") (pinfunction "35_35") (pintype "passive"))
      (node (ref "J2") (pin "35") (pinfunction "35_35") (pintype "passive"))
      (node (ref "J3") (pin "35") (pinfunction "35_35") (pintype "passive"))
      (node (ref "J4") (pin "35") (pinfunction "35_35") (pintype "passive"))
      (node (ref "U2") (pin "6") (pinfunction "S4_6") (pintype "passive"))
    )
    (net (code "85") (name "/BREQ#") (class "Default")
      (node (ref "J1") (pin "36") (pinfunction "36_36") (pintype "passive"))
      (node (ref "J2") (pin "36") (pinfunction "36_36") (pintype "passive"))
      (node (ref "J3") (pin "36") (pinfunction "36_36") (pintype "passive"))
      (node (ref "J4") (pin "36") (pinfunction "36_36") (pintype "passive"))
      (node (ref "U2") (pin "5") (pinfunction "S3_5") (pintype "passive"))
    )
    (net (code "86") (name "/CS0#") (class "Default")
      (node (ref "J1") (pin "48") (pinfunction "48_48") (pintype "passive"))
      (node (ref "J2") (pin "48") (pinfunction "48_48") (pintype "passive"))
      (node (ref "J3") (pin "48") (pinfunction "48_48") (pintype "passive"))
      (node (ref "J4") (pin "48") (pinfunction "48_48") (pintype "passive"))
    )
    (net (code "87") (name "/CS1#") (class "Default")
      (node (ref "J1") (pin "49") (pinfunction "49_49") (pintype "passive"))
      (node (ref "J2") (pin "49") (pinfunction "49_49") (pintype "passive"))
      (node (ref "J3") (pin "49") (pinfunction "49_49") (pintype "passive"))
      (node (ref "J4") (pin "49") (pinfunction "49_49") (pintype "passive"))
    )
    (net (code "88") (name "/CS2#") (class "Default")
      (node (ref "J1") (pin "50") (pinfunction "50_50") (pintype "passive"))
      (node (ref "J2") (pin "50") (pinfunction "50_50") (pintype "passive"))
      (node (ref "J3") (pin "50") (pinfunction "50_50") (pintype "passive"))
      (node (ref "J4") (pin "50") (pinfunction "50_50") (pintype "passive"))
    )
    (net (code "89") (name "/CS3#") (class "Default")
      (node (ref "J1") (pin "51") (pinfunction "51_51") (pintype "passive"))
      (node (ref "J2") (pin "51") (pinfunction "51_51") (pintype "passive"))
      (node (ref "J3") (pin "51") (pinfunction "51_51") (pintype "passive"))
      (node (ref "J4") (pin "51") (pinfunction "51_51") (pintype "passive"))
    )
    (net (code "90") (name "/D0") (class "Default")
      (node (ref "J1") (pin "40") (pinfunction "40_40") (pintype "passive"))
      (node (ref "J2") (pin "40") (pinfunction "40_40") (pintype "passive"))
      (node (ref "J3") (pin "40") (pinfunction "40_40") (pintype "passive"))
      (node (ref "J4") (pin "40") (pinfunction "40_40") (pintype "passive"))
      (node (ref "U1") (pin "23") (pinfunction "S21_23") (pintype "passive"))
    )
    (net (code "91") (name "/D1") (class "Default")
      (node (ref "J1") (pin "41") (pinfunction "41_41") (pintype "passive"))
      (node (ref "J2") (pin "41") (pinfunction "41_41") (pintype "passive"))
      (node (ref "J3") (pin "41") (pinfunction "41_41") (pintype "passive"))
      (node (ref "J4") (pin "41") (pinfunction "41_41") (pintype "passive"))
      (node (ref "U1") (pin "22") (pinfunction "S20_22") (pintype "passive"))
    )
    (net (code "92") (name "/D2") (class "Default")
      (node (ref "J1") (pin "42") (pinfunction "42_42") (pintype "passive"))
      (node (ref "J2") (pin "42") (pinfunction "42_42") (pintype "passive"))
      (node (ref "J3") (pin "42") (pinfunction "42_42") (pintype "passive"))
      (node (ref "J4") (pin "42") (pinfunction "42_42") (pintype "passive"))
      (node (ref "U1") (pin "21") (pinfunction "S19_21") (pintype "passive"))
    )
    (net (code "93") (name "/D3") (class "Default")
      (node (ref "J1") (pin "43") (pinfunction "43_43") (pintype "passive"))
      (node (ref "J2") (pin "43") (pinfunction "43_43") (pintype "passive"))
      (node (ref "J3") (pin "43") (pinfunction "43_43") (pintype "passive"))
      (node (ref "J4") (pin "43") (pinfunction "43_43") (pintype "passive"))
      (node (ref "U1") (pin "20") (pinfunction "S18_20") (pintype "passive"))
    )
    (net (code "94") (name "/D4") (class "Default")
      (node (ref "J1") (pin "44") (pinfunction "44_44") (pintype "passive"))
      (node (ref "J2") (pin "44") (pinfunction "44_44") (pintype "passive"))
      (node (ref "J3") (pin "44") (pinfunction "44_44") (pintype "passive"))
      (node (ref "J4") (pin "44") (pinfunction "44_44") (pintype "passive"))
      (node (ref "U1") (pin "19") (pinfunction "S17_19") (pintype "passive"))
    )
    (net (code "95") (name "/D5") (class "Default")
      (node (ref "J1") (pin "45") (pinfunction "45_45") (pintype "passive"))
      (node (ref "J2") (pin "45") (pinfunction "45_45") (pintype "passive"))
      (node (ref "J3") (pin "45") (pinfunction "45_45") (pintype "passive"))
      (node (ref "J4") (pin "45") (pinfunction "45_45") (pintype "passive"))
      (node (ref "U1") (pin "18") (pinfunction "S16_18") (pintype "passive"))
    )
    (net (code "96") (name "/D6") (class "Default")
      (node (ref "J1") (pin "46") (pinfunction "46_46") (pintype "passive"))
      (node (ref "J2") (pin "46") (pinfunction "46_46") (pintype "passive"))
      (node (ref "J3") (pin "46") (pinfunction "46_46") (pintype "passive"))
      (node (ref "J4") (pin "46") (pinfunction "46_46") (pintype "passive"))
      (node (ref "U1") (pin "17") (pinfunction "S15_17") (pintype "passive"))
    )
    (net (code "97") (name "/D7") (class "Default")
      (node (ref "J1") (pin "47") (pinfunction "47_47") (pintype "passive"))
      (node (ref "J2") (pin "47") (pinfunction "47_47") (pintype "passive"))
      (node (ref "J3") (pin "47") (pinfunction "47_47") (pintype "passive"))
      (node (ref "J4") (pin "47") (pinfunction "47_47") (pintype "passive"))
      (node (ref "U1") (pin "16") (pinfunction "S14_16") (pintype "passive"))
    )
    (net (code "98") (name "/FCPU") (class "Default")
      (node (ref "J1") (pin "34") (pinfunction "34_34") (pintype "passive"))
      (node (ref "J2") (pin "34") (pinfunction "34_34") (pintype "passive"))
      (node (ref "J3") (pin "34") (pinfunction "34_34") (pintype "passive"))
      (node (ref "J4") (pin "34") (pinfunction "34_34") (pintype "passive"))
      (node (ref "U2") (pin "7") (pinfunction "S5_7") (pintype "passive"))
    )
    (net (code "99") (name "/HALT#") (class "Default")
      (node (ref "J1") (pin "39") (pinfunction "39_39") (pintype "passive"))
      (node (ref "J2") (pin "39") (pinfunction "39_39") (pintype "passive"))
      (node (ref "J3") (pin "39") (pinfunction "39_39") (pintype "passive"))
      (node (ref "J4") (pin "39") (pinfunction "39_39") (pintype "passive"))
      (node (ref "U1") (pin "24") (pinfunction "S22_24") (pintype "passive"))
    )
    (net (code "100") (name "/INST#") (class "Default")
      (node (ref "J1") (pin "33") (pinfunction "33_33") (pintype "passive"))
      (node (ref "J2") (pin "33") (pinfunction "33_33") (pintype "passive"))
      (node (ref "J3") (pin "33") (pinfunction "33_33") (pintype "passive"))
      (node (ref "J4") (pin "33") (pinfunction "33_33") (pintype "passive"))
      (node (ref "U2") (pin "8") (pinfunction "S6_8") (pintype "passive"))
    )
    (net (code "101") (name "/IO#") (class "Default")
      (node (ref "J1") (pin "30") (pinfunction "30_30") (pintype "passive"))
      (node (ref "J2") (pin "30") (pinfunction "30_30") (pintype "passive"))
      (node (ref "J3") (pin "30") (pinfunction "30_30") (pintype "passive"))
      (node (ref "J4") (pin "30") (pinfunction "30_30") (pintype "passive"))
      (node (ref "U2") (pin "11") (pinfunction "S9_11") (pintype "passive"))
    )
    (net (code "102") (name "/MEM#") (class "Default")
      (node (ref "J1") (pin "29") (pinfunction "29_29") (pintype "passive"))
      (node (ref "J2") (pin "29") (pinfunction "29_29") (pintype "passive"))
      (node (ref "J3") (pin "29") (pinfunction "29_29") (pintype "passive"))
      (node (ref "J4") (pin "29") (pinfunction "29_29") (pintype "passive"))
      (node (ref "U2") (pin "12") (pinfunction "S10_12") (pintype "passive"))
    )
    (net (code "103") (name "/NMI#") (class "Default")
      (node (ref "J1") (pin "38") (pinfunction "38_38") (pintype "passive"))
      (node (ref "J2") (pin "38") (pinfunction "38_38") (pintype "passive"))
      (node (ref "J3") (pin "38") (pinfunction "38_38") (pintype "passive"))
      (node (ref "J4") (pin "38") (pinfunction "38_38") (pintype "passive"))
      (node (ref "U2") (pin "3") (pinfunction "S1_3") (pintype "passive"))
    )
    (net (code "104") (name "/PB0") (class "Default")
      (node (ref "J1") (pin "52") (pinfunction "52_52") (pintype "passive"))
      (node (ref "J2") (pin "52") (pinfunction "52_52") (pintype "passive"))
      (node (ref "J3") (pin "52") (pinfunction "52_52") (pintype "passive"))
      (node (ref "J4") (pin "52") (pinfunction "52_52") (pintype "passive"))
      (node (ref "U3") (pin "15") (pinfunction "S13_15") (pintype "passive"))
    )
    (net (code "105") (name "/PB4") (class "Default")
      (node (ref "J1") (pin "53") (pinfunction "53_53") (pintype "passive"))
      (node (ref "J2") (pin "53") (pinfunction "53_53") (pintype "passive"))
      (node (ref "J3") (pin "53") (pinfunction "53_53") (pintype "passive"))
      (node (ref "J4") (pin "53") (pinfunction "53_53") (pintype "passive"))
      (node (ref "U1") (pin "5") (pinfunction "S3_5") (pintype "passive"))
    )
    (net (code "106") (name "/PB5") (class "Default")
      (node (ref "J1") (pin "54") (pinfunction "54_54") (pintype "passive"))
      (node (ref "J2") (pin "54") (pinfunction "54_54") (pintype "passive"))
      (node (ref "J3") (pin "54") (pinfunction "54_54") (pintype "passive"))
      (node (ref "J4") (pin "54") (pinfunction "54_54") (pintype "passive"))
      (node (ref "U1") (pin "4") (pinfunction "S2_4") (pintype "passive"))
    )
    (net (code "107") (name "/PC0") (class "Default")
      (node (ref "J1") (pin "55") (pinfunction "55_55") (pintype "passive"))
      (node (ref "J2") (pin "55") (pinfunction "55_55") (pintype "passive"))
      (node (ref "J3") (pin "55") (pinfunction "55_55") (pintype "passive"))
      (node (ref "J4") (pin "55") (pinfunction "55_55") (pintype "passive"))
      (node (ref "U1") (pin "15") (pinfunction "S13_15") (pintype "passive"))
    )
    (net (code "108") (name "/PC1") (class "Default")
      (node (ref "J1") (pin "56") (pinfunction "56_56") (pintype "passive"))
      (node (ref "J2") (pin "56") (pinfunction "56_56") (pintype "passive"))
      (node (ref "J3") (pin "56") (pinfunction "56_56") (pintype "passive"))
      (node (ref "J4") (pin "56") (pinfunction "56_56") (pintype "passive"))
      (node (ref "U1") (pin "14") (pinfunction "S12_14") (pintype "passive"))
    )
    (net (code "109") (name "/PD0") (class "Default")
      (node (ref "J1") (pin "57") (pinfunction "57_57") (pintype "passive"))
      (node (ref "J2") (pin "57") (pinfunction "57_57") (pintype "passive"))
      (node (ref "J3") (pin "57") (pinfunction "57_57") (pintype "passive"))
      (node (ref "J4") (pin "57") (pinfunction "57_57") (pintype "passive"))
      (node (ref "U1") (pin "13") (pinfunction "S11_13") (pintype "passive"))
    )
    (net (code "110") (name "/PD1") (class "Default")
      (node (ref "J1") (pin "58") (pinfunction "58_58") (pintype "passive"))
      (node (ref "J2") (pin "58") (pinfunction "58_58") (pintype "passive"))
      (node (ref "J3") (pin "58") (pinfunction "58_58") (pintype "passive"))
      (node (ref "J4") (pin "58") (pinfunction "58_58") (pintype "passive"))
      (node (ref "U1") (pin "12") (pinfunction "S10_12") (pintype "passive"))
    )
    (net (code "111") (name "/PD2") (class "Default")
      (node (ref "J1") (pin "59") (pinfunction "59_59") (pintype "passive"))
      (node (ref "J2") (pin "59") (pinfunction "59_59") (pintype "passive"))
      (node (ref "J3") (pin "59") (pinfunction "59_59") (pintype "passive"))
      (node (ref "J4") (pin "59") (pinfunction "59_59") (pintype "passive"))
      (node (ref "U1") (pin "11") (pinfunction "S9_11") (pintype "passive"))
    )
    (net (code "112") (name "/PD3") (class "Default")
      (node (ref "J1") (pin "60") (pinfunction "60_60") (pintype "passive"))
      (node (ref "J2") (pin "60") (pinfunction "60_60") (pintype "passive"))
      (node (ref "J3") (pin "60") (pinfunction "60_60") (pintype "passive"))
      (node (ref "J4") (pin "60") (pinfunction "60_60") (pintype "passive"))
      (node (ref "U1") (pin "10") (pinfunction "S8_10") (pintype "passive"))
    )
    (net (code "113") (name "/PD4") (class "Default")
      (node (ref "J1") (pin "61") (pinfunction "61_61") (pintype "passive"))
      (node (ref "J2") (pin "61") (pinfunction "61_61") (pintype "passive"))
      (node (ref "J3") (pin "61") (pinfunction "61_61") (pintype "passive"))
      (node (ref "J4") (pin "61") (pinfunction "61_61") (pintype "passive"))
      (node (ref "U1") (pin "9") (pinfunction "S7_9") (pintype "passive"))
    )
    (net (code "114") (name "/PD5") (class "Default")
      (node (ref "J1") (pin "62") (pinfunction "62_62") (pintype "passive"))
      (node (ref "J2") (pin "62") (pinfunction "62_62") (pintype "passive"))
      (node (ref "J3") (pin "62") (pinfunction "62_62") (pintype "passive"))
      (node (ref "J4") (pin "62") (pinfunction "62_62") (pintype "passive"))
      (node (ref "U1") (pin "8") (pinfunction "S6_8") (pintype "passive"))
    )
    (net (code "115") (name "/PD6") (class "Default")
      (node (ref "J1") (pin "63") (pinfunction "63_63") (pintype "passive"))
      (node (ref "J2") (pin "63") (pinfunction "63_63") (pintype "passive"))
      (node (ref "J3") (pin "63") (pinfunction "63_63") (pintype "passive"))
      (node (ref "J4") (pin "63") (pinfunction "63_63") (pintype "passive"))
      (node (ref "U1") (pin "7") (pinfunction "S5_7") (pintype "passive"))
    )
    (net (code "116") (name "/PD7") (class "Default")
      (node (ref "J1") (pin "64") (pinfunction "64_64") (pintype "passive"))
      (node (ref "J2") (pin "64") (pinfunction "64_64") (pintype "passive"))
      (node (ref "J3") (pin "64") (pinfunction "64_64") (pintype "passive"))
      (node (ref "J4") (pin "64") (pinfunction "64_64") (pintype "passive"))
      (node (ref "U1") (pin "6") (pinfunction "S4_6") (pintype "passive"))
    )
    (net (code "117") (name "/RD#") (class "Default")
      (node (ref "J1") (pin "31") (pinfunction "31_31") (pintype "passive"))
      (node (ref "J2") (pin "31") (pinfunction "31_31") (pintype "passive"))
      (node (ref "J3") (pin "31") (pinfunction "31_31") (pintype "passive"))
      (node (ref "J4") (pin "31") (pinfunction "31_31") (pintype "passive"))
      (node (ref "U2") (pin "10") (pinfunction "S8_10") (pintype "passive"))
    )
    (net (code "118") (name "/RST#") (class "Default")
      (node (ref "J1") (pin "68") (pinfunction "68_68") (pintype "passive"))
      (node (ref "J2") (pin "68") (pinfunction "68_68") (pintype "passive"))
      (node (ref "J3") (pin "68") (pinfunction "68_68") (pintype "passive"))
      (node (ref "J4") (pin "68") (pinfunction "68_68") (pintype "passive"))
      (node (ref "U1") (pin "3") (pinfunction "S1_3") (pintype "passive"))
    )
    (net (code "119") (name "/SCL") (class "Default")
      (node (ref "J1") (pin "65") (pinfunction "65_65") (pintype "passive"))
      (node (ref "J2") (pin "65") (pinfunction "65_65") (pintype "passive"))
      (node (ref "J3") (pin "65") (pinfunction "65_65") (pintype "passive"))
      (node (ref "J4") (pin "65") (pinfunction "65_65") (pintype "passive"))
    )
    (net (code "120") (name "/SDA") (class "Default")
      (node (ref "J1") (pin "66") (pinfunction "66_66") (pintype "passive"))
      (node (ref "J2") (pin "66") (pinfunction "66_66") (pintype "passive"))
      (node (ref "J3") (pin "66") (pinfunction "66_66") (pintype "passive"))
      (node (ref "J4") (pin "66") (pinfunction "66_66") (pintype "passive"))
    )
    (net (code "121") (name "/SND") (class "Default")
      (node (ref "J1") (pin "67") (pinfunction "67_67") (pintype "passive"))
      (node (ref "J2") (pin "67") (pinfunction "67_67") (pintype "passive"))
      (node (ref "J3") (pin "67") (pinfunction "67_67") (pintype "passive"))
      (node (ref "J4") (pin "67") (pinfunction "67_67") (pintype "passive"))
    )
    (net (code "122") (name "/WAIT#") (class "Default")
      (node (ref "J1") (pin "37") (pinfunction "37_37") (pintype "passive"))
      (node (ref "J2") (pin "37") (pinfunction "37_37") (pintype "passive"))
      (node (ref "J3") (pin "37") (pinfunction "37_37") (pintype "passive"))
      (node (ref "J4") (pin "37") (pinfunction "37_37") (pintype "passive"))
      (node (ref "U2") (pin "4") (pinfunction "S2_4") (pintype "passive"))
    )
    (net (code "123") (name "/WR#") (class "Default")
      (node (ref "J1") (pin "32") (pinfunction "32_32") (pintype "passive"))
      (node (ref "J2") (pin "32") (pinfunction "32_32") (pintype "passive"))
      (node (ref "J3") (pin "32") (pinfunction "32_32") (pintype "passive"))
      (node (ref "J4") (pin "32") (pinfunction "32_32") (pintype "passive"))
      (node (ref "U2") (pin "9") (pinfunction "S7_9") (pintype "passive"))
    )
    (net (code "124") (name "GND") (class "Default")
      (node (ref "C1") (pin "2") (pintype "passive"))
      (node (ref "C10") (pin "2") (pintype "passive"))
      (node (ref "C11") (pin "2") (pintype "passive"))
      (node (ref "C12") (pin "2") (pintype "passive"))
      (node (ref "C2") (pin "2") (pintype "passive"))
      (node (ref "C3") (pin "2") (pintype "passive"))
      (node (ref "C4") (pin "2") (pintype "passive"))
      (node (ref "C5") (pin "1") (pintype "passive"))
      (node (ref "C6") (pin "1") (pintype "passive"))
      (node (ref "C7") (pin "1") (pintype "passive"))
      (node (ref "C8") (pin "2") (pintype "passive"))
      (node (ref "C9") (pin "2") (pintype "passive"))
      (node (ref "J1") (pin "1") (pinfunction "1_1") (pintype "passive"))
      (node (ref "J1") (pin "2") (pinfunction "2_2") (pintype "passive"))
      (node (ref "J1") (pin "71") (pinfunction "71_71") (pintype "passive"))
      (node (ref "J1") (pin "72") (pinfunction "72_72") (pintype "passive"))
      (node (ref "J2") (pin "1") (pinfunction "1_1") (pintype "passive"))
      (node (ref "J2") (pin "2") (pinfunction "2_2") (pintype "passive"))
      (node (ref "J2") (pin "71") (pinfunction "71_71") (pintype "passive"))
      (node (ref "J2") (pin "72") (pinfunction "72_72") (pintype "passive"))
      (node (ref "J3") (pin "1") (pinfunction "1_1") (pintype "passive"))
      (node (ref "J3") (pin "2") (pinfunction "2_2") (pintype "passive"))
      (node (ref "J3") (pin "71") (pinfunction "71_71") (pintype "passive"))
      (node (ref "J3") (pin "72") (pinfunction "72_72") (pintype "passive"))
      (node (ref "J4") (pin "1") (pinfunction "1_1") (pintype "passive"))
      (node (ref "J4") (pin "2") (pinfunction "2_2") (pintype "passive"))
      (node (ref "J4") (pin "71") (pinfunction "71_71") (pintype "passive"))
      (node (ref "J4") (pin "72") (pinfunction "72_72") (pintype "passive"))
      (node (ref "U1") (pin "1") (pinfunction "GND_1") (pintype "passive"))
      (node (ref "U2") (pin "1") (pinfunction "GND_1") (pintype "passive"))
      (node (ref "U3") (pin "1") (pinfunction "GND_1") (pintype "passive"))
      (node (ref "U3") (pin "16") (pinfunction "S14_16") (pintype "passive"))
      (node (ref "U3") (pin "17") (pinfunction "S15_17") (pintype "passive"))
      (node (ref "U3") (pin "18") (pinfunction "S16_18") (pintype "passive"))
      (node (ref "U3") (pin "19") (pinfunction "S17_19") (pintype "passive"))
      (node (ref "U3") (pin "20") (pinfunction "S18_20") (pintype "passive"))
      (node (ref "U3") (pin "21") (pinfunction "S19_21") (pintype "passive"))
      (node (ref "U3") (pin "22") (pinfunction "S20_22") (pintype "passive"))
      (node (ref "U3") (pin "23") (pinfunction "S21_23") (pintype "passive"))
      (node (ref "U3") (pin "24") (pinfunction "S22_24") (pintype "passive"))
      (node (ref "U3") (pin "25") (pinfunction "D22_25") (pintype "passive"))
      (node (ref "U3") (pin "26") (pinfunction "D21_26") (pintype "passive"))
      (node (ref "U3") (pin "27") (pinfunction "D20_27") (pintype "passive"))
      (node (ref "U3") (pin "28") (pinfunction "D19_28") (pintype "passive"))
      (node (ref "U3") (pin "29") (pinfunction "D18_29") (pintype "passive"))
      (node (ref "U3") (pin "30") (pinfunction "D17_30") (pintype "passive"))
      (node (ref "U3") (pin "31") (pinfunction "D16_31") (pintype "passive"))
      (node (ref "U3") (pin "32") (pinfunction "D15_32") (pintype "passive"))
      (node (ref "U3") (pin "33") (pinfunction "D14_33") (pintype "passive"))
      (node (ref "U4") (pin "1") (pinfunction "G_1") (pintype "passive"))
      (node (ref "X1") (pin "17") (pinfunction "17_17") (pintype "passive"))
      (node (ref "X2") (pin "17") (pinfunction "17_17") (pintype "passive"))
      (node (ref "X3") (pin "17") (pinfunction "17_17") (pintype "passive"))
      (node (ref "X4") (pin "17") (pinfunction "17_17") (pintype "passive"))
      (node (ref "X5") (pin "17") (pinfunction "17_17") (pintype "passive"))
      (node (ref "X6") (pin "17") (pinfunction "17_17") (pintype "passive"))
    )
    (net (code "125") (name "Net-(U1-Dref)") (class "Default")
      (node (ref "C8") (pin "1") (pintype "passive"))
      (node (ref "R1") (pin "2") (pintype "passive"))
      (node (ref "U1") (pin "47") (pinfunction "Dref_47") (pintype "passive"))
      (node (ref "U1") (pin "48") (pinfunction "Gref_48") (pintype "passive"))
    )
    (net (code "126") (name "Net-(U2-Dref)") (class "Default")
      (node (ref "C9") (pin "1") (pintype "passive"))
      (node (ref "R2") (pin "2") (pintype "passive"))
      (node (ref "U2") (pin "47") (pinfunction "Dref_47") (pintype "passive"))
      (node (ref "U2") (pin "48") (pinfunction "Gref_48") (pintype "passive"))
    )
    (net (code "127") (name "Net-(U3-Dref)") (class "Default")
      (node (ref "C10") (pin "1") (pintype "passive"))
      (node (ref "R3") (pin "2") (pintype "passive"))
      (node (ref "U3") (pin "47") (pinfunction "Dref_47") (pintype "passive"))
      (node (ref "U3") (pin "48") (pinfunction "Gref_48") (pintype "passive"))
    )
    (net (code "128") (name "unconnected-(J1-Pad69)") (class "Default")
      (node (ref "J1") (pin "69") (pinfunction "69_69") (pintype "passive+no_connect"))
    )
    (net (code "129") (name "unconnected-(J1-Pad70)") (class "Default")
      (node (ref "J1") (pin "70") (pinfunction "70_70") (pintype "passive+no_connect"))
    )
    (net (code "130") (name "unconnected-(J2-Pad69)") (class "Default")
      (node (ref "J2") (pin "69") (pinfunction "69_69") (pintype "passive+no_connect"))
    )
    (net (code "131") (name "unconnected-(J2-Pad70)") (class "Default")
      (node (ref "J2") (pin "70") (pinfunction "70_70") (pintype "passive+no_connect"))
    )
    (net (code "132") (name "unconnected-(J3-Pad69)") (class "Default")
      (node (ref "J3") (pin "69") (pinfunction "69_69") (pintype "passive+no_connect"))
    )
    (net (code "133") (name "unconnected-(J3-Pad70)") (class "Default")
      (node (ref "J3") (pin "70") (pinfunction "70_70") (pintype "passive+no_connect"))
    )
    (net (code "134") (name "unconnected-(J4-Pad69)") (class "Default")
      (node (ref "J4") (pin "69") (pinfunction "69_69") (pintype "passive+no_connect"))
    )
    (net (code "135") (name "unconnected-(J4-Pad70)") (class "Default")
      (node (ref "J4") (pin "70") (pinfunction "70_70") (pintype "passive+no_connect"))
    )
    (net (code "136") (name "unconnected-(X4-Pad1)") (class "Default")
      (node (ref "X4") (pin "1") (pinfunction "1_1") (pintype "passive+no_connect"))
    )
    (net (code "137") (name "unconnected-(X4-Pad2)") (class "Default")
      (node (ref "X4") (pin "2") (pinfunction "2_2") (pintype "passive+no_connect"))
    )
    (net (code "138") (name "unconnected-(X4-Pad3)") (class "Default")
      (node (ref "X4") (pin "3") (pinfunction "3_3") (pintype "passive+no_connect"))
    )
    (net (code "139") (name "unconnected-(X4-Pad4)") (class "Default")
      (node (ref "X4") (pin "4") (pinfunction "4_4") (pintype "passive+no_connect"))
    )
    (net (code "140") (name "unconnected-(X4-Pad5)") (class "Default")
      (node (ref "X4") (pin "5") (pinfunction "5_5") (pintype "passive+no_connect"))
    )
    (net (code "141") (name "unconnected-(X4-Pad6)") (class "Default")
      (node (ref "X4") (pin "6") (pinfunction "6_6") (pintype "passive+no_connect"))
    )
    (net (code "142") (name "unconnected-(X4-Pad7)") (class "Default")
      (node (ref "X4") (pin "7") (pinfunction "7_7") (pintype "passive+no_connect"))
    )
    (net (code "143") (name "unconnected-(X4-Pad8)") (class "Default")
      (node (ref "X4") (pin "8") (pinfunction "8_8") (pintype "passive+no_connect"))
    )
    (net (code "144") (name "unconnected-(X4-Pad19)") (class "Default")
      (node (ref "X4") (pin "19") (pinfunction "19_19") (pintype "passive+no_connect"))
    )
    (net (code "145") (name "unconnected-(X4-Pad27)") (class "Default")
      (node (ref "X4") (pin "27") (pinfunction "27_27") (pintype "passive+no_connect"))
    )
    (net (code "146") (name "unconnected-(X4-Pad28)") (class "Default")
      (node (ref "X4") (pin "28") (pinfunction "28_28") (pintype "passive+no_connect"))
    )
    (net (code "147") (name "unconnected-(X4-Pad29)") (class "Default")
      (node (ref "X4") (pin "29") (pinfunction "29_29") (pintype "passive+no_connect"))
    )
    (net (code "148") (name "unconnected-(X4-Pad30)") (class "Default")
      (node (ref "X4") (pin "30") (pinfunction "30_30") (pintype "passive+no_connect"))
    )
    (net (code "149") (name "unconnected-(X4-Pad31)") (class "Default")
      (node (ref "X4") (pin "31") (pinfunction "31_31") (pintype "passive+no_connect"))
    )
    (net (code "150") (name "unconnected-(X4-Pad32)") (class "Default")
      (node (ref "X4") (pin "32") (pinfunction "32_32") (pintype "passive+no_connect"))
    )
    (net (code "151") (name "unconnected-(X4-Pad33)") (class "Default")
      (node (ref "X4") (pin "33") (pinfunction "33_33") (pintype "passive+no_connect"))
    )
    (net (code "152") (name "unconnected-(X4-Pad34)") (class "Default")
      (node (ref "X4") (pin "34") (pinfunction "34_34") (pintype "passive+no_connect"))
    )
    (net (code "153") (name "unconnected-(X5-Pad1)") (class "Default")
      (node (ref "X5") (pin "1") (pinfunction "1_1") (pintype "passive+no_connect"))
    )
    (net (code "154") (name "unconnected-(X5-Pad2)") (class "Default")
      (node (ref "X5") (pin "2") (pinfunction "2_2") (pintype "passive+no_connect"))
    )
    (net (code "155") (name "unconnected-(X5-Pad3)") (class "Default")
      (node (ref "X5") (pin "3") (pinfunction "3_3") (pintype "passive+no_connect"))
    )
    (net (code "156") (name "unconnected-(X5-Pad4)") (class "Default")
      (node (ref "X5") (pin "4") (pinfunction "4_4") (pintype "passive+no_connect"))
    )
    (net (code "157") (name "unconnected-(X5-Pad5)") (class "Default")
      (node (ref "X5") (pin "5") (pinfunction "5_5") (pintype "passive+no_connect"))
    )
    (net (code "158") (name "unconnected-(X5-Pad6)") (class "Default")
      (node (ref "X5") (pin "6") (pinfunction "6_6") (pintype "passive+no_connect"))
    )
    (net (code "159") (name "unconnected-(X5-Pad7)") (class "Default")
      (node (ref "X5") (pin "7") (pinfunction "7_7") (pintype "passive+no_connect"))
    )
    (net (code "160") (name "unconnected-(X5-Pad8)") (class "Default")
      (node (ref "X5") (pin "8") (pinfunction "8_8") (pintype "passive+no_connect"))
    )
    (net (code "161") (name "unconnected-(X5-Pad19)") (class "Default")
      (node (ref "X5") (pin "19") (pinfunction "19_19") (pintype "passive+no_connect"))
    )
    (net (code "162") (name "unconnected-(X5-Pad27)") (class "Default")
      (node (ref "X5") (pin "27") (pinfunction "27_27") (pintype "passive+no_connect"))
    )
    (net (code "163") (name "unconnected-(X5-Pad28)") (class "Default")
      (node (ref "X5") (pin "28") (pinfunction "28_28") (pintype "passive+no_connect"))
    )
    (net (code "164") (name "unconnected-(X5-Pad29)") (class "Default")
      (node (ref "X5") (pin "29") (pinfunction "29_29") (pintype "passive+no_connect"))
    )
    (net (code "165") (name "unconnected-(X5-Pad30)") (class "Default")
      (node (ref "X5") (pin "30") (pinfunction "30_30") (pintype "passive+no_connect"))
    )
    (net (code "166") (name "unconnected-(X5-Pad31)") (class "Default")
      (node (ref "X5") (pin "31") (pinfunction "31_31") (pintype "passive+no_connect"))
    )
    (net (code "167") (name "unconnected-(X5-Pad32)") (class "Default")
      (node (ref "X5") (pin "32") (pinfunction "32_32") (pintype "passive+no_connect"))
    )
    (net (code "168") (name "unconnected-(X5-Pad33)") (class "Default")
      (node (ref "X5") (pin "33") (pinfunction "33_33") (pintype "passive+no_connect"))
    )
    (net (code "169") (name "unconnected-(X5-Pad34)") (class "Default")
      (node (ref "X5") (pin "34") (pinfunction "34_34") (pintype "passive+no_connect"))
    )
    (net (code "170") (name "unconnected-(X6-Pad1)") (class "Default")
      (node (ref "X6") (pin "1") (pinfunction "1_1") (pintype "passive+no_connect"))
    )
    (net (code "171") (name "unconnected-(X6-Pad2)") (class "Default")
      (node (ref "X6") (pin "2") (pinfunction "2_2") (pintype "passive+no_connect"))
    )
    (net (code "172") (name "unconnected-(X6-Pad3)") (class "Default")
      (node (ref "X6") (pin "3") (pinfunction "3_3") (pintype "passive+no_connect"))
    )
    (net (code "173") (name "unconnected-(X6-Pad4)") (class "Default")
      (node (ref "X6") (pin "4") (pinfunction "4_4") (pintype "passive+no_connect"))
    )
    (net (code "174") (name "unconnected-(X6-Pad5)") (class "Default")
      (node (ref "X6") (pin "5") (pinfunction "5_5") (pintype "passive+no_connect"))
    )
    (net (code "175") (name "unconnected-(X6-Pad6)") (class "Default")
      (node (ref "X6") (pin "6") (pinfunction "6_6") (pintype "passive+no_connect"))
    )
    (net (code "176") (name "unconnected-(X6-Pad7)") (class "Default")
      (node (ref "X6") (pin "7") (pinfunction "7_7") (pintype "passive+no_connect"))
    )
    (net (code "177") (name "unconnected-(X6-Pad8)") (class "Default")
      (node (ref "X6") (pin "8") (pinfunction "8_8") (pintype "passive+no_connect"))
    )
    (net (code "178") (name "unconnected-(X6-Pad19)") (class "Default")
      (node (ref "X6") (pin "19") (pinfunction "19_19") (pintype "passive+no_connect"))
    )
    (net (code "179") (name "unconnected-(X6-Pad27)") (class "Default")
      (node (ref "X6") (pin "27") (pinfunction "27_27") (pintype "passive+no_connect"))
    )
    (net (code "180") (name "unconnected-(X6-Pad28)") (class "Default")
      (node (ref "X6") (pin "28") (pinfunction "28_28") (pintype "passive+no_connect"))
    )
    (net (code "181") (name "unconnected-(X6-Pad29)") (class "Default")
      (node (ref "X6") (pin "29") (pinfunction "29_29") (pintype "passive+no_connect"))
    )
    (net (code "182") (name "unconnected-(X6-Pad30)") (class "Default")
      (node (ref "X6") (pin "30") (pinfunction "30_30") (pintype "passive+no_connect"))
    )
    (net (code "183") (name "unconnected-(X6-Pad31)") (class "Default")
      (node (ref "X6") (pin "31") (pinfunction "31_31") (pintype "passive+no_connect"))
    )
    (net (code "184") (name "unconnected-(X6-Pad32)") (class "Default")
      (node (ref "X6") (pin "32") (pinfunction "32_32") (pintype "passive+no_connect"))
    )
    (net (code "185") (name "unconnected-(X6-Pad33)") (class "Default")
      (node (ref "X6") (pin "33") (pinfunction "33_33") (pintype "passive+no_connect"))
    )
    (net (code "186") (name "unconnected-(X6-Pad34)") (class "Default")
      (node (ref "X6") (pin "34") (pinfunction "34_34") (pintype "passive+no_connect"))
    )
  )
)
